# MainBoard.net
KiCad netlist of a schematic drawn in EAGLE
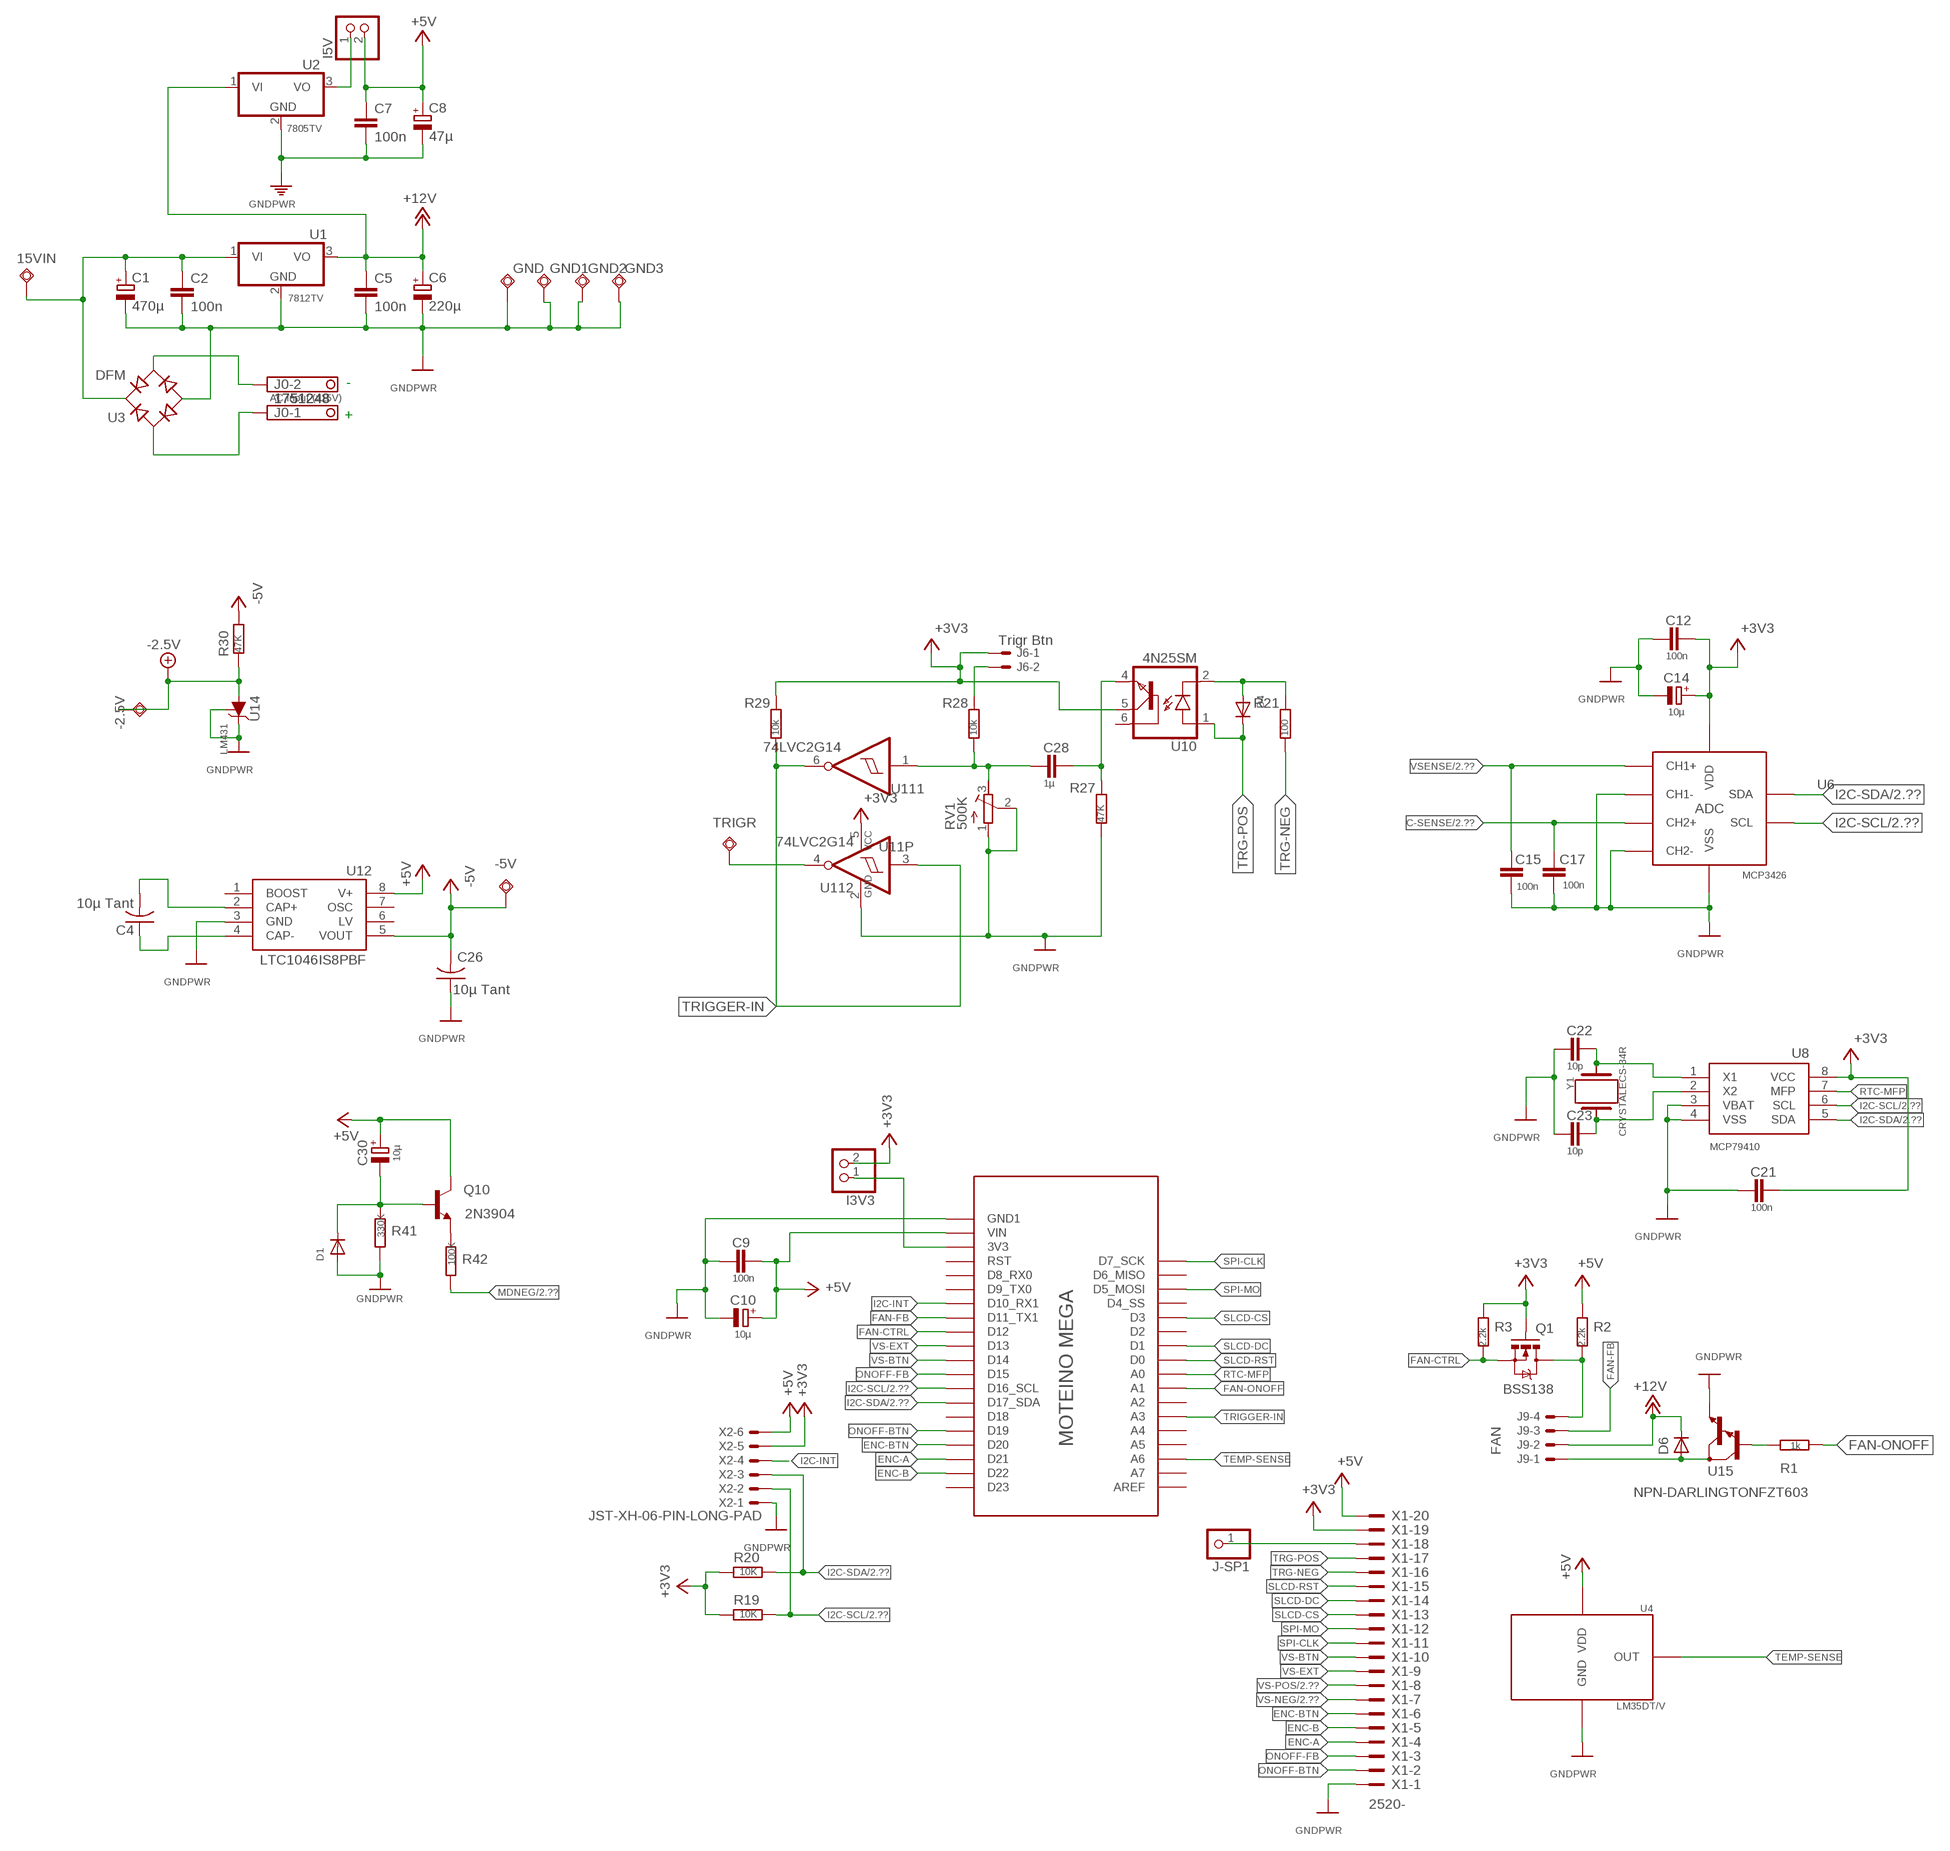
[diagram p0: schematic, sheet 1]
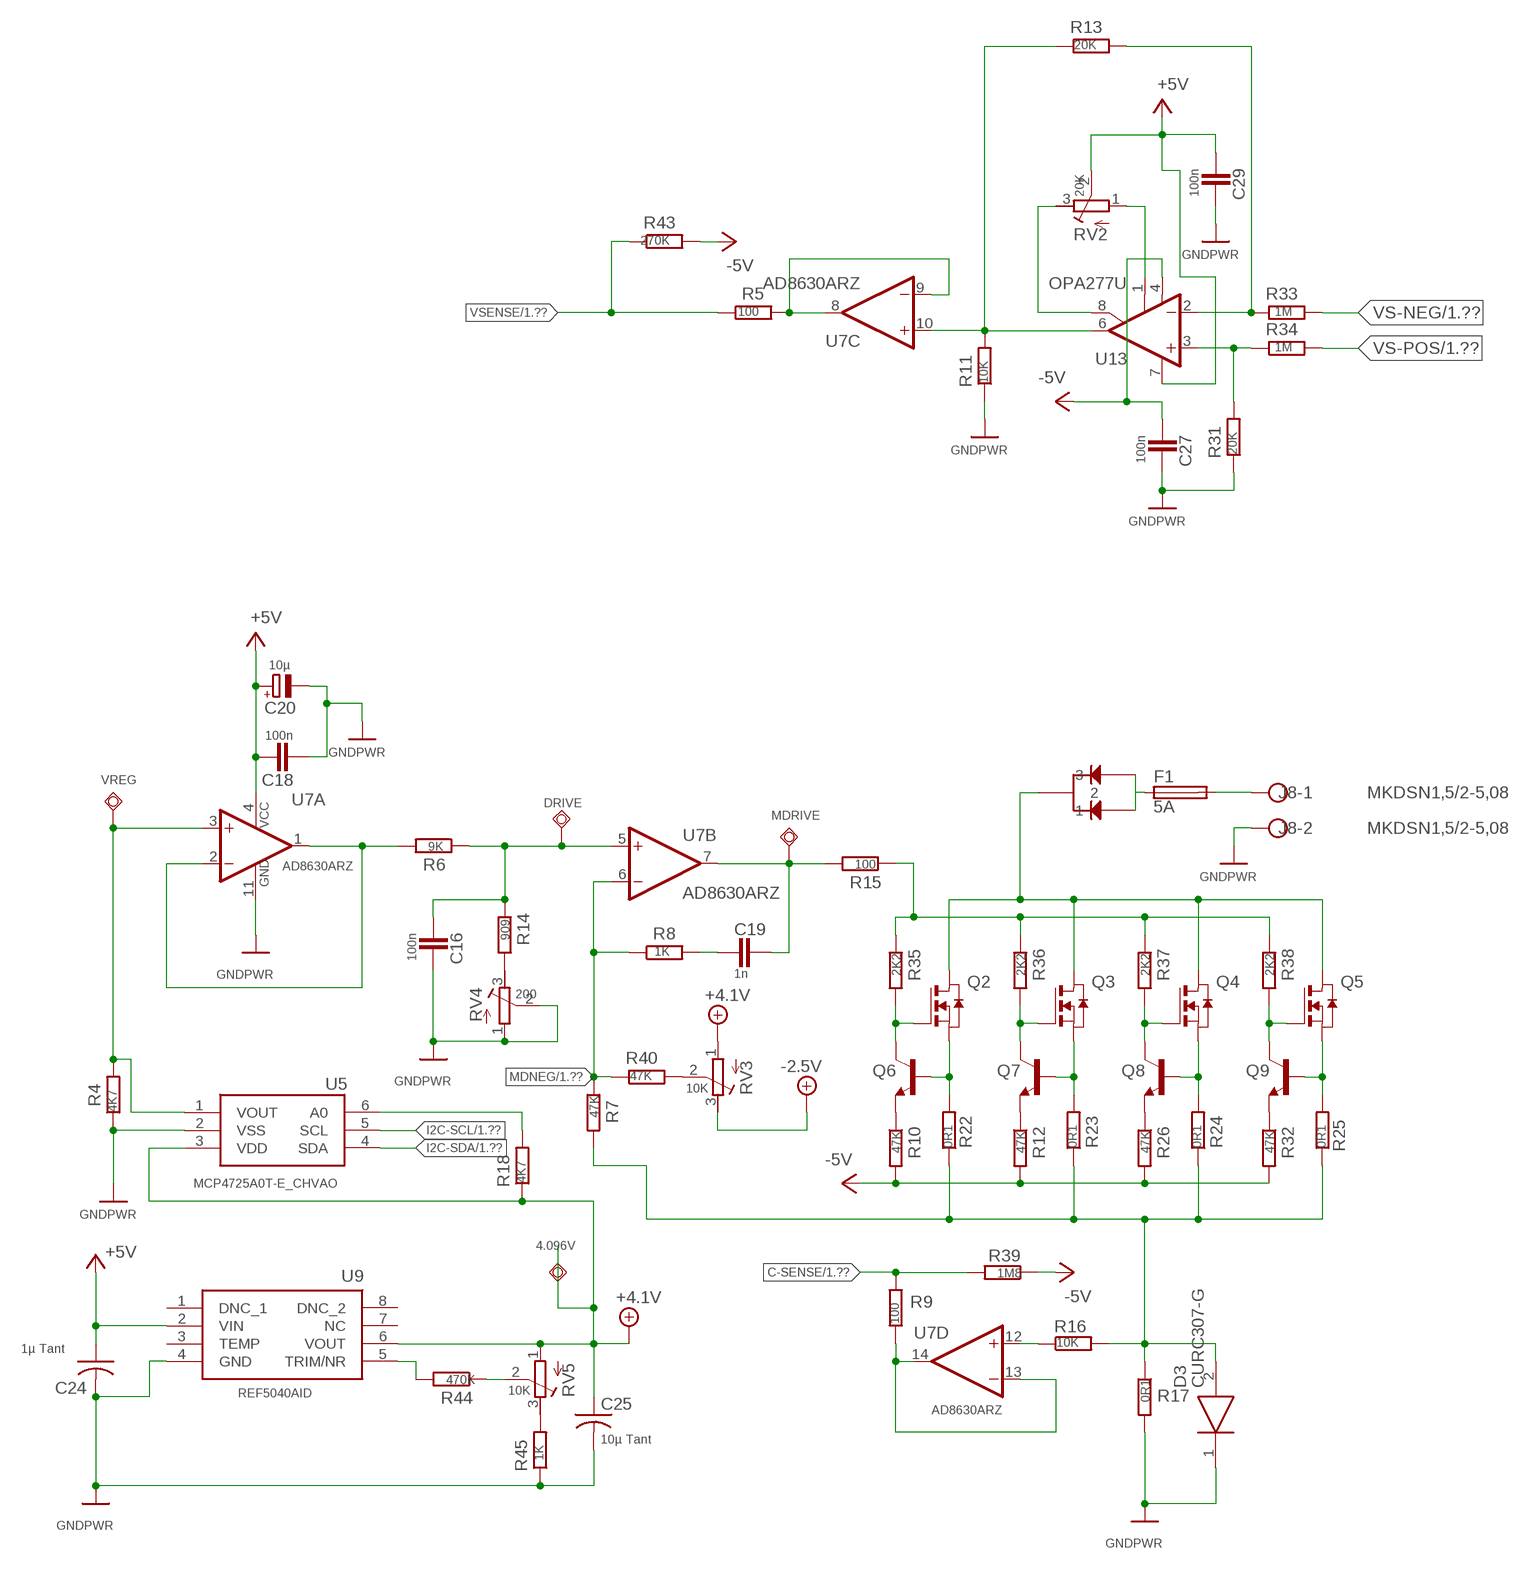
[diagram p1: schematic, sheet 2]

(export (version "E")
  (design (tool "Eeschema 10.0.6"))
  (components
    (comp (ref "4.096V")
      (value "TEST-POINT4952")
      (footprint "eagle-import:TP-KEYSTONE-4952")
      (libsource (lib "eagle-import") (part "TEST-POINT4952"))
    )
    (comp (ref "C16")
      (value "100n")
      (footprint "eagle-import:C0805K")
      (libsource (lib "eagle-import") (part "C-EUC0805K"))
    )
    (comp (ref "C18")
      (value "100n")
      (footprint "eagle-import:C0805K")
      (libsource (lib "eagle-import") (part "C-EUC0805K"))
    )
    (comp (ref "C19")
      (value "1n")
      (footprint "eagle-import:C0805K")
      (libsource (lib "eagle-import") (part "C-EUC0805K"))
    )
    (comp (ref "C20")
      (value "10µ")
      (footprint "eagle-import:E2-5")
      (libsource (lib "eagle-import") (part "CPOL-EUE2-5"))
    )
    (comp (ref "C24")
      (value "1µ Tant")
      (footprint "eagle-import:C1210")
      (libsource (lib "eagle-import") (part "C-USC1210"))
    )
    (comp (ref "C25")
      (value "10µ Tant")
      (footprint "eagle-import:C1210")
      (libsource (lib "eagle-import") (part "C-USC1210"))
    )
    (comp (ref "C27")
      (value "100n")
      (footprint "eagle-import:C0805K")
      (libsource (lib "eagle-import") (part "C-EUC0805K"))
    )
    (comp (ref "C29")
      (value "100n")
      (footprint "eagle-import:C0805K")
      (libsource (lib "eagle-import") (part "C-EUC0805K"))
    )
    (comp (ref "D3")
      (value "CURC307-G")
      (footprint "eagle-import:DIOM7959X262N")
      (fields (field (name "MOUSER_PART_NUMBER") "750-CURC307-G"))
      (libsource (lib "eagle-import") (part "CURC307-G"))
    )
    (comp (ref "D5")
      (value "MBR41H100CT/V")
      (footprint "eagle-import:TO220-VERT")
      (libsource (lib "eagle-import") (part "MBR41H100CT/V"))
    )
    (comp (ref "DRIVE")
      (value "TEST-POINT4952")
      (footprint "eagle-import:TP-KEYSTONE-4952")
      (libsource (lib "eagle-import") (part "TEST-POINT4952"))
    )
    (comp (ref "F1")
      (value "5A")
      (footprint "eagle-import:SHK20L")
      (libsource (lib "eagle-import") (part "SHK20L"))
    )
    (comp (ref "J8")
      (value "MKDSN1,5/2-5,08")
      (footprint "eagle-import:MKDSN1,5_2-5,08")
      (libsource (lib "eagle-import") (part "MKDSN1,5/2-5,08"))
    )
    (comp (ref "MDRIVE")
      (value "TEST-POINT4952")
      (footprint "eagle-import:TP-KEYSTONE-4952")
      (libsource (lib "eagle-import") (part "TEST-POINT4952"))
    )
    (comp (ref "Q2")
      (value "SUP70040E/V")
      (footprint "eagle-import:TO220-VERT")
      (libsource (lib "eagle-import") (part "SUP70040E/V"))
    )
    (comp (ref "Q3")
      (value "SUP70040E/V")
      (footprint "eagle-import:TO220-VERT")
      (libsource (lib "eagle-import") (part "SUP70040E/V"))
    )
    (comp (ref "Q4")
      (value "SUP70040E/V")
      (footprint "eagle-import:TO220-VERT")
      (libsource (lib "eagle-import") (part "SUP70040E/V"))
    )
    (comp (ref "Q5")
      (value "SUP70040E/V")
      (footprint "eagle-import:TO220-VERT")
      (libsource (lib "eagle-import") (part "SUP70040E/V"))
    )
    (comp (ref "Q6")
      (value "MPS2222A-NPN-TO92-CBE")
      (footprint "eagle-import:TO92-CBE")
      (libsource (lib "eagle-import") (part "-NPN-TO92-CBEMPS2222A"))
    )
    (comp (ref "Q7")
      (value "MPS2222A-NPN-TO92-CBE")
      (footprint "eagle-import:TO92-CBE")
      (libsource (lib "eagle-import") (part "-NPN-TO92-CBEMPS2222A"))
    )
    (comp (ref "Q8")
      (value "MPS2222A-NPN-TO92-CBE")
      (footprint "eagle-import:TO92-CBE")
      (libsource (lib "eagle-import") (part "-NPN-TO92-CBEMPS2222A"))
    )
    (comp (ref "Q9")
      (value "MPS2222A-NPN-TO92-CBE")
      (footprint "eagle-import:TO92-CBE")
      (libsource (lib "eagle-import") (part "-NPN-TO92-CBEMPS2222A"))
    )
    (comp (ref "R4")
      (value "4K7")
      (footprint "eagle-import:R0805")
      (libsource (lib "eagle-import") (part "R-EU_R0805"))
    )
    (comp (ref "R5")
      (value "100")
      (footprint "eagle-import:R0805")
      (libsource (lib "eagle-import") (part "R-EU_R0805"))
    )
    (comp (ref "R6")
      (value "9K")
      (footprint "eagle-import:R0805")
      (libsource (lib "eagle-import") (part "R-EU_R0805"))
    )
    (comp (ref "R7")
      (value "47K")
      (footprint "eagle-import:R0805")
      (libsource (lib "eagle-import") (part "R-EU_R0805"))
    )
    (comp (ref "R8")
      (value "1K")
      (footprint "eagle-import:R0805")
      (libsource (lib "eagle-import") (part "R-EU_R0805"))
    )
    (comp (ref "R9")
      (value "100")
      (footprint "eagle-import:R0805")
      (libsource (lib "eagle-import") (part "R-EU_R0805"))
    )
    (comp (ref "R10")
      (value "47K")
      (footprint "eagle-import:R0805")
      (libsource (lib "eagle-import") (part "R-EU_R0805"))
    )
    (comp (ref "R11")
      (value "10K")
      (footprint "eagle-import:R0805")
      (libsource (lib "eagle-import") (part "R-EU_R0805"))
    )
    (comp (ref "R12")
      (value "47K")
      (footprint "eagle-import:R0805")
      (libsource (lib "eagle-import") (part "R-EU_R0805"))
    )
    (comp (ref "R13")
      (value "20K")
      (footprint "eagle-import:R1206")
      (libsource (lib "eagle-import") (part "R-EU_R1206"))
    )
    (comp (ref "R14")
      (value "909")
      (footprint "eagle-import:R1206")
      (libsource (lib "eagle-import") (part "R-EU_R1206"))
    )
    (comp (ref "R15")
      (value "100")
      (footprint "eagle-import:R0805")
      (libsource (lib "eagle-import") (part "R-EU_R0805"))
    )
    (comp (ref "R16")
      (value "10K")
      (footprint "eagle-import:R0805")
      (libsource (lib "eagle-import") (part "R-EU_R0805"))
    )
    (comp (ref "R17")
      (value "0R1")
      (footprint "eagle-import:TO220-DPAC")
      (libsource (lib "eagle-import") (part "PWR220T-35"))
    )
    (comp (ref "R18")
      (value "4K7")
      (footprint "eagle-import:R0805")
      (libsource (lib "eagle-import") (part "R-EU_R0805"))
    )
    (comp (ref "R22")
      (value "0R1")
      (footprint "eagle-import:0750V")
      (libsource (lib "eagle-import") (part "RESISTOR0750V"))
    )
    (comp (ref "R23")
      (value "0R1")
      (footprint "eagle-import:0750V")
      (libsource (lib "eagle-import") (part "RESISTOR0750V"))
    )
    (comp (ref "R24")
      (value "0R1")
      (footprint "eagle-import:0750V")
      (libsource (lib "eagle-import") (part "RESISTOR0750V"))
    )
    (comp (ref "R25")
      (value "0R1")
      (footprint "eagle-import:0750V")
      (libsource (lib "eagle-import") (part "RESISTOR0750V"))
    )
    (comp (ref "R26")
      (value "47K")
      (footprint "eagle-import:R0805")
      (libsource (lib "eagle-import") (part "R-EU_R0805"))
    )
    (comp (ref "R31")
      (value "20K")
      (footprint "eagle-import:R1206")
      (libsource (lib "eagle-import") (part "R-EU_R1206"))
    )
    (comp (ref "R32")
      (value "47K")
      (footprint "eagle-import:R0805")
      (libsource (lib "eagle-import") (part "R-EU_R0805"))
    )
    (comp (ref "R33")
      (value "1M")
      (footprint "eagle-import:R1206")
      (libsource (lib "eagle-import") (part "R-EU_R1206"))
    )
    (comp (ref "R34")
      (value "1M")
      (footprint "eagle-import:R1206")
      (libsource (lib "eagle-import") (part "R-EU_R1206"))
    )
    (comp (ref "R35")
      (value "2K2")
      (footprint "eagle-import:R0805")
      (libsource (lib "eagle-import") (part "R-EU_R0805"))
    )
    (comp (ref "R36")
      (value "2K2")
      (footprint "eagle-import:R0805")
      (libsource (lib "eagle-import") (part "R-EU_R0805"))
    )
    (comp (ref "R37")
      (value "2K2")
      (footprint "eagle-import:R0805")
      (libsource (lib "eagle-import") (part "R-EU_R0805"))
    )
    (comp (ref "R38")
      (value "2K2")
      (footprint "eagle-import:R0805")
      (libsource (lib "eagle-import") (part "R-EU_R0805"))
    )
    (comp (ref "R39")
      (value "1M8")
      (footprint "eagle-import:R0805")
      (libsource (lib "eagle-import") (part "R-EU_R0805"))
    )
    (comp (ref "R40")
      (value "47K")
      (footprint "eagle-import:R1206")
      (libsource (lib "eagle-import") (part "R-EU_R1206"))
    )
    (comp (ref "R43")
      (value "270K")
      (footprint "eagle-import:R0805")
      (libsource (lib "eagle-import") (part "R-EU_R0805"))
    )
    (comp (ref "R44")
      (value "470K")
      (footprint "eagle-import:R0805")
      (libsource (lib "eagle-import") (part "R-EU_R0805"))
    )
    (comp (ref "R45")
      (value "1K")
      (footprint "eagle-import:R0805")
      (libsource (lib "eagle-import") (part "R-EU_R0805"))
    )
    (comp (ref "RV2")
      (value "20K")
      (footprint "eagle-import:RTRIM3296W")
      (libsource (lib "eagle-import") (part "R-TRIMM3296W"))
    )
    (comp (ref "RV3")
      (value "10K")
      (footprint "eagle-import:RTRIM3296W")
      (libsource (lib "eagle-import") (part "R-TRIMM3296W"))
    )
    (comp (ref "RV4")
      (value "200")
      (footprint "eagle-import:RTRIM3296W")
      (libsource (lib "eagle-import") (part "R-TRIMM3296W"))
    )
    (comp (ref "RV5")
      (value "10K")
      (footprint "eagle-import:RTRIM3296W")
      (libsource (lib "eagle-import") (part "R-TRIMM3296W"))
    )
    (comp (ref "U5")
      (value "MCP4725A0T-E_CHVAO")
      (footprint "eagle-import:SOT95P270X145-6N")
      (fields
        (field (name "MANUFACTURER_PART_NUMBER") "MCP4725A0T-E/CHVAO")
        (field (name "MOUSER_PART_NUMBER") "579-MCP4725A0TECHVAO")
      )
      (libsource (lib "eagle-import") (part "MCP4725A0T-E_CHVAO"))
    )
    (comp (ref "U7")
      (value "AD8630ARZ")
      (footprint "eagle-import:SO14")
      (libsource (lib "eagle-import") (part "AD8630ARZ"))
    )
    (comp (ref "U9")
      (value "REF5040AID")
      (footprint "eagle-import:SOIC127P600X175-8N")
      (fields (field (name "MOUSER_PART_NUMBER") "595-REF5040AID") (field (name "RS_PART_NUMBER") "0404326P"))
      (libsource (lib "eagle-import") (part "REF5040AID"))
    )
    (comp (ref "U13")
      (value "OPA277U")
      (footprint "eagle-import:SO08")
      (libsource (lib "eagle-import") (part "OPA277U"))
    )
    (comp (ref "VREG")
      (value "TEST-POINT4952")
      (footprint "eagle-import:TP-KEYSTONE-4952")
      (libsource (lib "eagle-import") (part "TEST-POINT4952"))
    )
    (comp (ref "-2.5V")
      (value "TEST-POINT4952")
      (footprint "eagle-import:TP-KEYSTONE-4952")
      (libsource (lib "eagle-import") (part "TEST-POINT4952"))
    )
    (comp (ref "-5V")
      (value "TEST-POINT4952")
      (footprint "eagle-import:TP-KEYSTONE-4952")
      (libsource (lib "eagle-import") (part "TEST-POINT4952"))
    )
    (comp (ref "15VIN")
      (value "TEST-POINT4952")
      (footprint "eagle-import:TP-KEYSTONE-4952")
      (libsource (lib "eagle-import") (part "TEST-POINT4952"))
    )
    (comp (ref "C1")
      (value "470µ")
      (footprint "eagle-import:E5-10,5")
      (libsource (lib "eagle-import") (part "CPOL-EUE5-10.5"))
    )
    (comp (ref "C2")
      (value "100n")
      (footprint "eagle-import:C0805K")
      (libsource (lib "eagle-import") (part "C-EUC0805K"))
    )
    (comp (ref "C4")
      (value "10µ Tant")
      (footprint "eagle-import:C1210")
      (libsource (lib "eagle-import") (part "C-USC1210"))
    )
    (comp (ref "C5")
      (value "100n")
      (footprint "eagle-import:C0805K")
      (libsource (lib "eagle-import") (part "C-EUC0805K"))
    )
    (comp (ref "C6")
      (value "220µ")
      (footprint "eagle-import:E5-10,5")
      (libsource (lib "eagle-import") (part "CPOL-EUE5-10.5"))
    )
    (comp (ref "C7")
      (value "100n")
      (footprint "eagle-import:C0805K")
      (libsource (lib "eagle-import") (part "C-EUC0805K"))
    )
    (comp (ref "C8")
      (value "47µ")
      (footprint "eagle-import:E5-5")
      (libsource (lib "eagle-import") (part "CPOL-EUE5-5"))
    )
    (comp (ref "C9")
      (value "100n")
      (footprint "eagle-import:C0805K")
      (libsource (lib "eagle-import") (part "C-EUC0805K"))
    )
    (comp (ref "C10")
      (value "10µ")
      (footprint "eagle-import:E2-5")
      (libsource (lib "eagle-import") (part "CPOL-EUE2-5"))
    )
    (comp (ref "C12")
      (value "100n")
      (footprint "eagle-import:C0805K")
      (libsource (lib "eagle-import") (part "C-EUC0805K"))
    )
    (comp (ref "C14")
      (value "10µ")
      (footprint "eagle-import:E2-5")
      (libsource (lib "eagle-import") (part "CPOL-EUE2-5"))
    )
    (comp (ref "C15")
      (value "100n")
      (footprint "eagle-import:C0805K")
      (libsource (lib "eagle-import") (part "C-EUC0805K"))
    )
    (comp (ref "C17")
      (value "100n")
      (footprint "eagle-import:C0805K")
      (libsource (lib "eagle-import") (part "C-EUC0805K"))
    )
    (comp (ref "C21")
      (value "100n")
      (footprint "eagle-import:C0805K")
      (libsource (lib "eagle-import") (part "C-EUC0805K"))
    )
    (comp (ref "C22")
      (value "10p")
      (footprint "eagle-import:C0805K")
      (libsource (lib "eagle-import") (part "C-EUC0805K"))
    )
    (comp (ref "C23")
      (value "10p")
      (footprint "eagle-import:C0805K")
      (libsource (lib "eagle-import") (part "C-EUC0805K"))
    )
    (comp (ref "C26")
      (value "10µ Tant")
      (footprint "eagle-import:C1210")
      (libsource (lib "eagle-import") (part "C-USC1210"))
    )
    (comp (ref "C28")
      (value "1µ")
      (footprint "eagle-import:C0805K")
      (libsource (lib "eagle-import") (part "C-EUC0805K"))
    )
    (comp (ref "C30")
      (value "10µ")
      (footprint "eagle-import:E2-5")
      (libsource (lib "eagle-import") (part "CPOL-EUE2-5"))
    )
    (comp (ref "D1")
      (value "DIODESOD-323F")
      (footprint "eagle-import:SOD-323F")
      (libsource (lib "eagle-import") (part "DIODESOD-323F"))
    )
    (comp (ref "D4")
      (value "DIODESOD-323F")
      (footprint "eagle-import:SOD-323F")
      (libsource (lib "eagle-import") (part "DIODESOD-323F"))
    )
    (comp (ref "D6")
      (value "DIODE_SOD-123FL")
      (footprint "eagle-import:SOD-123FL")
      (libsource (lib "eagle-import") (part "DIODE_SOD-123FL"))
    )
    (comp (ref "GND")
      (value "TEST-POINT4952")
      (footprint "eagle-import:TP-KEYSTONE-4952")
      (libsource (lib "eagle-import") (part "TEST-POINT4952"))
    )
    (comp (ref "GND1")
      (value "TEST-POINT4952")
      (footprint "eagle-import:TP-KEYSTONE-4952")
      (libsource (lib "eagle-import") (part "TEST-POINT4952"))
    )
    (comp (ref "GND2")
      (value "TEST-POINT4952")
      (footprint "eagle-import:TP-KEYSTONE-4952")
      (libsource (lib "eagle-import") (part "TEST-POINT4952"))
    )
    (comp (ref "GND3")
      (value "TEST-POINT4952")
      (footprint "eagle-import:TP-KEYSTONE-4952")
      (libsource (lib "eagle-import") (part "TEST-POINT4952"))
    )
    (comp (ref "I3V3")
      (value "PINHD-1X2")
      (footprint "eagle-import:1X02")
      (libsource (lib "eagle-import") (part "PINHD-1X2"))
    )
    (comp (ref "I5V")
      (value "PINHD-1X2")
      (footprint "eagle-import:1X02")
      (libsource (lib "eagle-import") (part "PINHD-1X2"))
    )
    (comp (ref "J-SP1")
      (value "PINHD-1X1")
      (footprint "eagle-import:1X01")
      (libsource (lib "eagle-import") (part "PINHD-1X1"))
    )
    (comp (ref "J0")
      (value "1751248")
      (footprint "eagle-import:1751248")
      (libsource (lib "eagle-import") (part "1751248"))
    )
    (comp (ref "J6")
      (value "Trigr Btn")
      (footprint "eagle-import:JST-XH-02-PACKAGE-ROUND-PAD")
      (libsource (lib "eagle-import") (part "JST-XH-02-PIN-ROUND-PAD"))
    )
    (comp (ref "J9")
      (value "FAN")
      (footprint "eagle-import:JST-XH-04-PACKAGE-ROUND-PAD")
      (libsource (lib "eagle-import") (part "JST-XH-04-PIN-ROUND-PAD"))
    )
    (comp (ref "Q1")
      (value "BSS138")
      (footprint "eagle-import:SOT23")
      (libsource (lib "eagle-import") (part "MOSFET-NCHANNELBSS138"))
    )
    (comp (ref "Q10")
      (value "2N3904")
      (footprint "eagle-import:TO92")
      (libsource (lib "eagle-import") (part "2N3904"))
    )
    (comp (ref "R1")
      (value "1k")
      (footprint "eagle-import:R0805")
      (libsource (lib "eagle-import") (part "R-EU_R0805"))
    )
    (comp (ref "R2")
      (value "2.2k")
      (footprint "eagle-import:R0805")
      (libsource (lib "eagle-import") (part "R-EU_R0805"))
    )
    (comp (ref "R3")
      (value "2.2k")
      (footprint "eagle-import:R0805")
      (libsource (lib "eagle-import") (part "R-EU_R0805"))
    )
    (comp (ref "R19")
      (value "10K")
      (footprint "eagle-import:R0805")
      (libsource (lib "eagle-import") (part "R-EU_R0805"))
    )
    (comp (ref "R20")
      (value "10K")
      (footprint "eagle-import:R0805")
      (libsource (lib "eagle-import") (part "R-EU_R0805"))
    )
    (comp (ref "R21")
      (value "100")
      (footprint "eagle-import:R0805")
      (libsource (lib "eagle-import") (part "R-EU_R0805"))
    )
    (comp (ref "R27")
      (value "47K")
      (footprint "eagle-import:R0805")
      (libsource (lib "eagle-import") (part "R-EU_R0805"))
    )
    (comp (ref "R28")
      (value "10k")
      (footprint "eagle-import:R0805")
      (libsource (lib "eagle-import") (part "R-EU_R0805"))
    )
    (comp (ref "R29")
      (value "10k")
      (footprint "eagle-import:R0805")
      (libsource (lib "eagle-import") (part "R-EU_R0805"))
    )
    (comp (ref "R30")
      (value "47K")
      (footprint "eagle-import:R0805")
      (libsource (lib "eagle-import") (part "R-EU_R0805"))
    )
    (comp (ref "R41")
      (value "330K")
      (footprint "eagle-import:R0805")
      (libsource (lib "eagle-import") (part "R-EU_R0805"))
    )
    (comp (ref "R42")
      (value "100K")
      (footprint "eagle-import:R0805")
      (libsource (lib "eagle-import") (part "R-EU_R0805"))
    )
    (comp (ref "RV1")
      (value "500K")
      (footprint "eagle-import:RTRIM3296W")
      (libsource (lib "eagle-import") (part "R-TRIMM3296W"))
    )
    (comp (ref "TRIGR")
      (value "TEST-POINT4952")
      (footprint "eagle-import:TP-KEYSTONE-4952")
      (libsource (lib "eagle-import") (part "TEST-POINT4952"))
    )
    (comp (ref "U$1")
      (value "MOTEINO_MEGA_SIMPLE")
      (footprint "eagle-import:MOTEINO_MEGA_SIMPLE")
      (libsource (lib "eagle-import") (part "MOTEINO_MEGA_SIMPLE"))
    )
    (comp (ref "U1")
      (value "7812TV")
      (footprint "eagle-import:TO220V")
      (libsource (lib "eagle-import") (part "78TV12"))
    )
    (comp (ref "U2")
      (value "7805TV")
      (footprint "eagle-import:TO220V")
      (libsource (lib "eagle-import") (part "78TV05"))
    )
    (comp (ref "U3")
      (value "DFM")
      (footprint "eagle-import:DFM")
      (libsource (lib "eagle-import") (part "DFM"))
    )
    (comp (ref "U4")
      (value "LM35DT/V")
      (footprint "eagle-import:TO220V")
      (libsource (lib "eagle-import") (part "LM35DT/V"))
    )
    (comp (ref "U6")
      (value "MCP3426")
      (footprint "eagle-import:SO8")
      (libsource (lib "eagle-import") (part "MCP3426"))
    )
    (comp (ref "U8")
      (value "MCP79410")
      (footprint "eagle-import:SOIC127P600X175-8N")
      (fields
        (field (name "MANUFACTURER_PART_NUMBER") "MCP79410-I/SN")
        (field (name "MOUSER_PART_NUMBER") "579-MCP79410-I/SN")
        (field (name "RS_PART_NUMBER") "7263949P")
      )
      (libsource (lib "eagle-import") (part "MCP79410-I_SN"))
    )
    (comp (ref "U10")
      (value "4N25SM")
      (footprint "eagle-import:DIL6-SMD")
      (fields (field (name "MF") "FAIRCHILD SEMICONDUCTOR"))
      (libsource (lib "eagle-import") (part "4N?MS25"))
    )
    (comp (ref "U11")
      (value "74LVC2G14")
      (footprint "eagle-import:SOT23-6")
      (libsource (lib "eagle-import") (part "74LVC2G14"))
    )
    (comp (ref "U12")
      (value "LTC1046IS8PBF")
      (footprint "eagle-import:SOIC127P599X175-8N")
      (libsource (lib "eagle-import") (part "LTC1046IS8PBF"))
    )
    (comp (ref "U14")
      (value "LM431")
      (footprint "eagle-import:SOT23")
      (libsource (lib "eagle-import") (part "LM431"))
    )
    (comp (ref "U15")
      (value "NPN-DARLINGTONFZT603")
      (footprint "eagle-import:SOT223")
      (libsource (lib "eagle-import") (part "NPN-DARLINGTONFZT603"))
    )
    (comp (ref "X1")
      (value "2520-")
      (footprint "eagle-import:PAK100_2500-20")
      (libsource (lib "eagle-import") (part "2520-"))
    )
    (comp (ref "X2")
      (value "JST-XH-06-PIN-LONG-PAD")
      (footprint "eagle-import:JST-XH-06-PACKAGE-LONG-PAD")
      (libsource (lib "eagle-import") (part "JST-XH-06-PIN-LONG-PAD"))
    )
    (comp (ref "Y1")
      (value "CRYSTALECS-34R")
      (footprint "eagle-import:ECS32712534RRTR")
      (libsource (lib "eagle-import") (part "CRYSTALECS-34R"))
    )
  )
  (nets
    (net (code "1") (name "+3V3") (class "Default")
      (node (ref "C12") (pin "1") (pinfunction "1_1") (pintype "passive"))
      (node (ref "C14") (pin "+") (pinfunction "+_+") (pintype "passive"))
      (node (ref "C21") (pin "1") (pinfunction "1_1") (pintype "passive"))
      (node (ref "I3V3") (pin "2") (pinfunction "2_2") (pintype "passive"))
      (node (ref "J6") (pin "1") (pinfunction "S_1") (pintype "passive"))
      (node (ref "Q1") (pin "1") (pinfunction "G_1") (pintype "passive"))
      (node (ref "R19") (pin "2") (pinfunction "2_2") (pintype "passive"))
      (node (ref "R20") (pin "2") (pinfunction "2_2") (pintype "passive"))
      (node (ref "R29") (pin "2") (pinfunction "2_2") (pintype "passive"))
      (node (ref "R3") (pin "2") (pinfunction "2_2") (pintype "passive"))
      (node (ref "U10") (pin "5") (pinfunction "COL_5") (pintype "passive"))
      (node (ref "U11") (pin "5") (pinfunction "VCC_5") (pintype "power_in"))
      (node (ref "U6") (pin "3") (pinfunction "VDD_3") (pintype "bidirectional"))
      (node (ref "U8") (pin "8") (pinfunction "VCC_8") (pintype "power_in"))
      (node (ref "X1") (pin "19") (pinfunction "KL_19") (pintype "passive"))
      (node (ref "X2") (pin "5") (pinfunction "S_5") (pintype "passive"))
    )
    (net (code "2") (name "+4.1V") (class "Default")
      (node (ref "4.096V") (pin "P$1") (pinfunction "TP_P$1") (pintype "bidirectional"))
      (node (ref "C25") (pin "1") (pinfunction "1_1") (pintype "passive"))
      (node (ref "R18") (pin "1") (pinfunction "1_1") (pintype "passive"))
      (node (ref "RV3") (pin "1") (pinfunction "A_1") (pintype "passive"))
      (node (ref "RV5") (pin "1") (pinfunction "A_1") (pintype "passive"))
      (node (ref "U5") (pin "3") (pinfunction "VDD_3") (pintype "bidirectional"))
      (node (ref "U9") (pin "6") (pinfunction "VOUT_6") (pintype "bidirectional"))
    )
    (net (code "3") (name "+5V") (class "Default")
      (node (ref "C10") (pin "+") (pinfunction "+_+") (pintype "passive"))
      (node (ref "C18") (pin "1") (pinfunction "1_1") (pintype "passive"))
      (node (ref "C20") (pin "+") (pinfunction "+_+") (pintype "passive"))
      (node (ref "C24") (pin "1") (pinfunction "1_1") (pintype "passive"))
      (node (ref "C29") (pin "2") (pinfunction "2_2") (pintype "passive"))
      (node (ref "C30") (pin "+") (pinfunction "+_+") (pintype "passive"))
      (node (ref "C7") (pin "1") (pinfunction "1_1") (pintype "passive"))
      (node (ref "C8") (pin "+") (pinfunction "+_+") (pintype "passive"))
      (node (ref "C9") (pin "1") (pinfunction "1_1") (pintype "passive"))
      (node (ref "I5V") (pin "2") (pinfunction "2_2") (pintype "passive"))
      (node (ref "Q10") (pin "1") (pinfunction "C_1") (pintype "passive"))
      (node (ref "R2") (pin "2") (pinfunction "2_2") (pintype "passive"))
      (node (ref "RV2") (pin "2") (pinfunction "S_2") (pintype "passive"))
      (node (ref "U$1") (pin "VIN") (pinfunction "VIN_VIN") (pintype "bidirectional"))
      (node (ref "U$1") (pin "VIN_2") (pinfunction "VIN_VIN_2") (pintype "bidirectional"))
      (node (ref "U12") (pin "8") (pinfunction "V+_8") (pintype "bidirectional"))
      (node (ref "U13") (pin "7") (pinfunction "V+_7") (pintype "power_in"))
      (node (ref "U4") (pin "1") (pinfunction "VDD_1") (pintype "power_in"))
      (node (ref "U7") (pin "4") (pinfunction "VCC_4") (pintype "power_in"))
      (node (ref "U9") (pin "2") (pinfunction "VIN_2") (pintype "bidirectional"))
      (node (ref "X1") (pin "20") (pinfunction "KL_20") (pintype "passive"))
      (node (ref "X2") (pin "6") (pinfunction "S_6") (pintype "passive"))
    )
    (net (code "4") (name "+12V") (class "Default")
      (node (ref "C5") (pin "1") (pinfunction "1_1") (pintype "passive"))
      (node (ref "C6") (pin "+") (pinfunction "+_+") (pintype "passive"))
      (node (ref "D6") (pin "C") (pinfunction "C_C") (pintype "passive"))
      (node (ref "J9") (pin "2") (pinfunction "S_2") (pintype "passive"))
      (node (ref "U1") (pin "3") (pinfunction "VO_3") (pintype "passive"))
      (node (ref "U2") (pin "1") (pinfunction "VI_1") (pintype "input"))
    )
    (net (code "5") (name "-2.5V") (class "Default")
      (node (ref "-2.5V") (pin "P$1") (pinfunction "TP_P$1") (pintype "bidirectional"))
      (node (ref "R30") (pin "1") (pinfunction "1_1") (pintype "passive"))
      (node (ref "RV3") (pin "3") (pinfunction "E_3") (pintype "passive"))
      (node (ref "U14") (pin "3") (pinfunction "A_3") (pintype "passive"))
    )
    (net (code "6") (name "-5V") (class "Default")
      (node (ref "-5V") (pin "P$1") (pinfunction "TP_P$1") (pintype "bidirectional"))
      (node (ref "C26") (pin "2") (pinfunction "2_2") (pintype "passive"))
      (node (ref "C27") (pin "2") (pinfunction "2_2") (pintype "passive"))
      (node (ref "R10") (pin "2") (pinfunction "2_2") (pintype "passive"))
      (node (ref "R12") (pin "2") (pinfunction "2_2") (pintype "passive"))
      (node (ref "R26") (pin "2") (pinfunction "2_2") (pintype "passive"))
      (node (ref "R30") (pin "2") (pinfunction "2_2") (pintype "passive"))
      (node (ref "R32") (pin "2") (pinfunction "2_2") (pintype "passive"))
      (node (ref "R39") (pin "1") (pinfunction "1_1") (pintype "passive"))
      (node (ref "R43") (pin "2") (pinfunction "2_2") (pintype "passive"))
      (node (ref "U12") (pin "5") (pinfunction "VOUT_5") (pintype "bidirectional"))
      (node (ref "U13") (pin "4") (pinfunction "V-_4") (pintype "power_in"))
    )
    (net (code "7") (name "C-SENSE") (class "Default")
      (node (ref "C17") (pin "2") (pinfunction "2_2") (pintype "passive"))
      (node (ref "R39") (pin "2") (pinfunction "2_2") (pintype "passive"))
      (node (ref "R9") (pin "2") (pinfunction "2_2") (pintype "passive"))
      (node (ref "U6") (pin "7") (pinfunction "CH2+_7") (pintype "bidirectional"))
    )
    (net (code "8") (name "ENC-A") (class "Default")
      (node (ref "U$1") (pin "D21") (pinfunction "D21_D21") (pintype "bidirectional"))
      (node (ref "X1") (pin "4") (pinfunction "KL_4") (pintype "passive"))
    )
    (net (code "9") (name "ENC-B") (class "Default")
      (node (ref "U$1") (pin "D22") (pinfunction "D22_D22") (pintype "bidirectional"))
      (node (ref "X1") (pin "5") (pinfunction "KL_5") (pintype "passive"))
    )
    (net (code "10") (name "ENC-BTN") (class "Default")
      (node (ref "U$1") (pin "D20") (pinfunction "D20_D20") (pintype "bidirectional"))
      (node (ref "X1") (pin "6") (pinfunction "KL_6") (pintype "passive"))
    )
    (net (code "11") (name "FAN-CTRL") (class "Default")
      (node (ref "Q1") (pin "2") (pinfunction "S_2") (pintype "passive"))
      (node (ref "R3") (pin "1") (pinfunction "1_1") (pintype "passive"))
      (node (ref "U$1") (pin "D12") (pinfunction "D12_D12") (pintype "bidirectional"))
    )
    (net (code "12") (name "FAN-FB") (class "Default")
      (node (ref "J9") (pin "3") (pinfunction "S_3") (pintype "passive"))
      (node (ref "U$1") (pin "D11") (pinfunction "D11_TX1_D11") (pintype "bidirectional"))
    )
    (net (code "13") (name "FAN-ONOFF") (class "Default")
      (node (ref "R1") (pin "1") (pinfunction "1_1") (pintype "passive"))
      (node (ref "U$1") (pin "A1") (pinfunction "A1_A1") (pintype "bidirectional"))
    )
    (net (code "14") (name "GND") (class "Default")
      (node (ref "C1") (pin "-") (pinfunction "-_-") (pintype "passive"))
      (node (ref "C10") (pin "-") (pinfunction "-_-") (pintype "passive"))
      (node (ref "C12") (pin "2") (pinfunction "2_2") (pintype "passive"))
      (node (ref "C14") (pin "-") (pinfunction "-_-") (pintype "passive"))
      (node (ref "C15") (pin "2") (pinfunction "2_2") (pintype "passive"))
      (node (ref "C16") (pin "1") (pinfunction "1_1") (pintype "passive"))
      (node (ref "C17") (pin "1") (pinfunction "1_1") (pintype "passive"))
      (node (ref "C18") (pin "2") (pinfunction "2_2") (pintype "passive"))
      (node (ref "C2") (pin "2") (pinfunction "2_2") (pintype "passive"))
      (node (ref "C20") (pin "-") (pinfunction "-_-") (pintype "passive"))
      (node (ref "C21") (pin "2") (pinfunction "2_2") (pintype "passive"))
      (node (ref "C22") (pin "2") (pinfunction "2_2") (pintype "passive"))
      (node (ref "C23") (pin "2") (pinfunction "2_2") (pintype "passive"))
      (node (ref "C24") (pin "2") (pinfunction "2_2") (pintype "passive"))
      (node (ref "C25") (pin "2") (pinfunction "2_2") (pintype "passive"))
      (node (ref "C26") (pin "1") (pinfunction "1_1") (pintype "passive"))
      (node (ref "C27") (pin "1") (pinfunction "1_1") (pintype "passive"))
      (node (ref "C29") (pin "1") (pinfunction "1_1") (pintype "passive"))
      (node (ref "C5") (pin "2") (pinfunction "2_2") (pintype "passive"))
      (node (ref "C6") (pin "-") (pinfunction "-_-") (pintype "passive"))
      (node (ref "C7") (pin "2") (pinfunction "2_2") (pintype "passive"))
      (node (ref "C8") (pin "-") (pinfunction "-_-") (pintype "passive"))
      (node (ref "C9") (pin "2") (pinfunction "2_2") (pintype "passive"))
      (node (ref "D1") (pin "A") (pinfunction "A_A") (pintype "passive"))
      (node (ref "D3") (pin "1") (pinfunction "K_1") (pintype "bidirectional"))
      (node (ref "GND") (pin "P$1") (pinfunction "TP_P$1") (pintype "bidirectional"))
      (node (ref "GND1") (pin "P$1") (pinfunction "TP_P$1") (pintype "bidirectional"))
      (node (ref "GND2") (pin "P$1") (pinfunction "TP_P$1") (pintype "bidirectional"))
      (node (ref "GND3") (pin "P$1") (pinfunction "TP_P$1") (pintype "bidirectional"))
      (node (ref "J8") (pin "2") (pinfunction "KL_2") (pintype "passive"))
      (node (ref "R11") (pin "1") (pinfunction "1_1") (pintype "passive"))
      (node (ref "R17") (pin "2") (pinfunction "2_2") (pintype "passive"))
      (node (ref "R27") (pin "1") (pinfunction "1_1") (pintype "passive"))
      (node (ref "R31") (pin "1") (pinfunction "1_1") (pintype "passive"))
      (node (ref "R4") (pin "1") (pinfunction "1_1") (pintype "passive"))
      (node (ref "R41") (pin "2") (pinfunction "2_2") (pintype "passive"))
      (node (ref "R45") (pin "1") (pinfunction "1_1") (pintype "passive"))
      (node (ref "RV1") (pin "1") (pinfunction "A_1") (pintype "passive"))
      (node (ref "RV1") (pin "2") (pinfunction "S_2") (pintype "passive"))
      (node (ref "RV4") (pin "1") (pinfunction "A_1") (pintype "passive"))
      (node (ref "RV4") (pin "2") (pinfunction "S_2") (pintype "passive"))
      (node (ref "U$1") (pin "GND1") (pinfunction "GND1_GND1") (pintype "bidirectional"))
      (node (ref "U$1") (pin "GND_2") (pinfunction "GND1_GND_2") (pintype "bidirectional"))
      (node (ref "U1") (pin "2") (pinfunction "GND_2") (pintype "passive"))
      (node (ref "U11") (pin "2") (pinfunction "GND_2") (pintype "power_in"))
      (node (ref "U12") (pin "3") (pinfunction "GND_3") (pintype "bidirectional"))
      (node (ref "U14") (pin "1") (pinfunction "C_1") (pintype "passive"))
      (node (ref "U14") (pin "2") (pinfunction "ADJ_2") (pintype "bidirectional"))
      (node (ref "U15") (pin "3") (pinfunction "E_3") (pintype "passive"))
      (node (ref "U2") (pin "2") (pinfunction "GND_2") (pintype "passive"))
      (node (ref "U3") (pin "-") (pinfunction "-_-") (pintype "passive"))
      (node (ref "U4") (pin "2") (pinfunction "GND_2") (pintype "power_in"))
      (node (ref "U5") (pin "2") (pinfunction "VSS_2") (pintype "bidirectional"))
      (node (ref "U6") (pin "2") (pinfunction "CH1-_2") (pintype "bidirectional"))
      (node (ref "U6") (pin "6") (pinfunction "VSS_6") (pintype "bidirectional"))
      (node (ref "U6") (pin "8") (pinfunction "CH2-_8") (pintype "bidirectional"))
      (node (ref "U7") (pin "11") (pinfunction "GND_11") (pintype "power_in"))
      (node (ref "U8") (pin "3") (pinfunction "VBAT_3") (pintype "bidirectional"))
      (node (ref "U8") (pin "4") (pinfunction "VSS_4") (pintype "power_in"))
      (node (ref "U9") (pin "4") (pinfunction "GND_4") (pintype "bidirectional"))
      (node (ref "X1") (pin "1") (pinfunction "KL_1") (pintype "passive"))
      (node (ref "X2") (pin "1") (pinfunction "S_1") (pintype "passive"))
    )
    (net (code "15") (name "I2C-INT") (class "Default")
      (node (ref "U$1") (pin "D10") (pinfunction "D10_RX1_D10") (pintype "bidirectional"))
      (node (ref "X2") (pin "4") (pinfunction "S_4") (pintype "passive"))
    )
    (net (code "16") (name "I2C-SCL") (class "Default")
      (node (ref "R19") (pin "1") (pinfunction "1_1") (pintype "passive"))
      (node (ref "U$1") (pin "D16") (pinfunction "D16_SCL_D16") (pintype "bidirectional"))
      (node (ref "U5") (pin "5") (pinfunction "SCL_5") (pintype "bidirectional"))
      (node (ref "U6") (pin "5") (pinfunction "SCL_5") (pintype "bidirectional"))
      (node (ref "U8") (pin "6") (pinfunction "SCL_6") (pintype "bidirectional"))
      (node (ref "X2") (pin "2") (pinfunction "S_2") (pintype "passive"))
    )
    (net (code "17") (name "I2C-SDA") (class "Default")
      (node (ref "R20") (pin "1") (pinfunction "1_1") (pintype "passive"))
      (node (ref "U$1") (pin "D17") (pinfunction "D17_SDA_D17") (pintype "bidirectional"))
      (node (ref "U5") (pin "4") (pinfunction "SDA_4") (pintype "bidirectional"))
      (node (ref "U6") (pin "4") (pinfunction "SDA_4") (pintype "bidirectional"))
      (node (ref "U8") (pin "5") (pinfunction "SDA_5") (pintype "bidirectional"))
      (node (ref "X2") (pin "3") (pinfunction "S_3") (pintype "passive"))
    )
    (net (code "18") (name "MDNEG") (class "Default")
      (node (ref "R40") (pin "1") (pinfunction "1_1") (pintype "passive"))
      (node (ref "R42") (pin "2") (pinfunction "2_2") (pintype "passive"))
      (node (ref "R7") (pin "1") (pinfunction "1_1") (pintype "passive"))
      (node (ref "R8") (pin "1") (pinfunction "1_1") (pintype "passive"))
      (node (ref "U7") (pin "6") (pinfunction "-IN_6") (pintype "input"))
    )
    (net (code "19") (name "Net-(15VIN-TP)") (class "Default")
      (node (ref "15VIN") (pin "P$1") (pinfunction "TP_P$1") (pintype "bidirectional"))
      (node (ref "C1") (pin "+") (pinfunction "+_+") (pintype "passive"))
      (node (ref "C2") (pin "1") (pinfunction "1_1") (pintype "passive"))
      (node (ref "U1") (pin "1") (pinfunction "VI_1") (pintype "input"))
      (node (ref "U3") (pin "+") (pinfunction "+_+") (pintype "passive"))
    )
    (net (code "20") (name "Net-(C19-Pad2)") (class "Default")
      (node (ref "C19") (pin "2") (pinfunction "2_2") (pintype "passive"))
      (node (ref "R8") (pin "2") (pinfunction "2_2") (pintype "passive"))
    )
    (net (code "21") (name "Net-(D3-A)") (class "Default")
      (node (ref "D3") (pin "2") (pinfunction "A_2") (pintype "bidirectional"))
      (node (ref "R16") (pin "2") (pinfunction "2_2") (pintype "passive"))
      (node (ref "R17") (pin "1") (pinfunction "1_1") (pintype "passive"))
      (node (ref "R22") (pin "1") (pinfunction "1_1") (pintype "passive"))
      (node (ref "R23") (pin "1") (pinfunction "1_1") (pintype "passive"))
      (node (ref "R24") (pin "1") (pinfunction "1_1") (pintype "passive"))
      (node (ref "R25") (pin "1") (pinfunction "1_1") (pintype "passive"))
      (node (ref "R7") (pin "2") (pinfunction "2_2") (pintype "passive"))
    )
    (net (code "22") (name "Net-(D5-Pad1)") (class "Default")
      (node (ref "D5") (pin "1") (pinfunction "1_1") (pintype "bidirectional"))
      (node (ref "D5") (pin "3") (pinfunction "3_3") (pintype "bidirectional"))
      (node (ref "F1") (pin "1A") (pinfunction "1_1A") (pintype "passive"))
      (node (ref "F1") (pin "1B") (pinfunction "1_1B") (pintype "passive"))
    )
    (net (code "23") (name "Net-(DRIVE-TP)") (class "Default")
      (node (ref "C16") (pin "2") (pinfunction "2_2") (pintype "passive"))
      (node (ref "DRIVE") (pin "P$1") (pinfunction "TP_P$1") (pintype "bidirectional"))
      (node (ref "R14") (pin "1") (pinfunction "1_1") (pintype "passive"))
      (node (ref "R6") (pin "1") (pinfunction "1_1") (pintype "passive"))
      (node (ref "U7") (pin "5") (pinfunction "+IN_5") (pintype "input"))
    )
    (net (code "24") (name "Net-(I3V3-Pad1)") (class "Default")
      (node (ref "I3V3") (pin "1") (pinfunction "1_1") (pintype "passive"))
      (node (ref "U$1") (pin "3V3") (pinfunction "3V3_3V3") (pintype "bidirectional"))
      (node (ref "U$1") (pin "3V3_2") (pinfunction "3V3_3V3_2") (pintype "bidirectional"))
    )
    (net (code "25") (name "Net-(J0A-K)") (class "Default")
      (node (ref "J0") (pin "1") (pinfunction "K_1") (pintype "passive"))
      (node (ref "U3") (pin "A1") (pinfunction "AC1_A1") (pintype "passive"))
    )
    (net (code "26") (name "Net-(J0B-K)") (class "Default")
      (node (ref "J0") (pin "2") (pinfunction "K_2") (pintype "passive"))
      (node (ref "U3") (pin "A2") (pinfunction "AC2_A2") (pintype "passive"))
    )
    (net (code "27") (name "Net-(J6B-S)") (class "Default")
      (node (ref "J6") (pin "2") (pinfunction "S_2") (pintype "passive"))
      (node (ref "R28") (pin "2") (pinfunction "2_2") (pintype "passive"))
    )
    (net (code "28") (name "Net-(J8A-KL)") (class "Default")
      (node (ref "F1") (pin "2A") (pinfunction "2_2A") (pintype "passive"))
      (node (ref "F1") (pin "2B") (pinfunction "2_2B") (pintype "passive"))
      (node (ref "J8") (pin "1") (pinfunction "KL_1") (pintype "passive"))
    )
    (net (code "29") (name "Net-(J9A-S)") (class "Default")
      (node (ref "D6") (pin "A") (pinfunction "A_A") (pintype "passive"))
      (node (ref "J9") (pin "1") (pinfunction "S_1") (pintype "passive"))
      (node (ref "U15") (pin "2") (pinfunction "C_2") (pintype "passive"))
      (node (ref "U15") (pin "4") (pinfunction "C_4") (pintype "passive"))
    )
    (net (code "30") (name "Net-(J9D-S)") (class "Default")
      (node (ref "J9") (pin "4") (pinfunction "S_4") (pintype "passive"))
      (node (ref "Q1") (pin "3") (pinfunction "D_3") (pintype "passive"))
      (node (ref "R2") (pin "1") (pinfunction "1_1") (pintype "passive"))
    )
    (net (code "31") (name "Net-(MDRIVE-TP)") (class "Default")
      (node (ref "C19") (pin "1") (pinfunction "1_1") (pintype "passive"))
      (node (ref "MDRIVE") (pin "P$1") (pinfunction "TP_P$1") (pintype "bidirectional"))
      (node (ref "R15") (pin "2") (pinfunction "2_2") (pintype "passive"))
      (node (ref "U7") (pin "7") (pinfunction "OUT_7") (pintype "output"))
    )
    (net (code "32") (name "Net-(Q2-D)") (class "Default")
      (node (ref "D5") (pin "2") (pinfunction "2_2") (pintype "bidirectional"))
      (node (ref "Q2") (pin "2") (pinfunction "D_2") (pintype "passive"))
      (node (ref "Q3") (pin "2") (pinfunction "D_2") (pintype "passive"))
      (node (ref "Q4") (pin "2") (pinfunction "D_2") (pintype "passive"))
      (node (ref "Q5") (pin "2") (pinfunction "D_2") (pintype "passive"))
    )
    (net (code "33") (name "Net-(Q2-G)") (class "Default")
      (node (ref "Q2") (pin "1") (pinfunction "G_1") (pintype "passive"))
      (node (ref "Q6") (pin "C") (pinfunction "C_C") (pintype "passive"))
      (node (ref "R35") (pin "2") (pinfunction "2_2") (pintype "passive"))
    )
    (net (code "34") (name "Net-(Q2-S)") (class "Default")
      (node (ref "Q2") (pin "3") (pinfunction "S_3") (pintype "passive"))
      (node (ref "Q6") (pin "B") (pinfunction "B_B") (pintype "passive"))
      (node (ref "R22") (pin "2") (pinfunction "2_2") (pintype "passive"))
    )
    (net (code "35") (name "Net-(Q3-G)") (class "Default")
      (node (ref "Q3") (pin "1") (pinfunction "G_1") (pintype "passive"))
      (node (ref "Q7") (pin "C") (pinfunction "C_C") (pintype "passive"))
      (node (ref "R36") (pin "2") (pinfunction "2_2") (pintype "passive"))
    )
    (net (code "36") (name "Net-(Q3-S)") (class "Default")
      (node (ref "Q3") (pin "3") (pinfunction "S_3") (pintype "passive"))
      (node (ref "Q7") (pin "B") (pinfunction "B_B") (pintype "passive"))
      (node (ref "R23") (pin "2") (pinfunction "2_2") (pintype "passive"))
    )
    (net (code "37") (name "Net-(Q4-G)") (class "Default")
      (node (ref "Q4") (pin "1") (pinfunction "G_1") (pintype "passive"))
      (node (ref "Q8") (pin "C") (pinfunction "C_C") (pintype "passive"))
      (node (ref "R37") (pin "2") (pinfunction "2_2") (pintype "passive"))
    )
    (net (code "38") (name "Net-(Q4-S)") (class "Default")
      (node (ref "Q4") (pin "3") (pinfunction "S_3") (pintype "passive"))
      (node (ref "Q8") (pin "B") (pinfunction "B_B") (pintype "passive"))
      (node (ref "R24") (pin "2") (pinfunction "2_2") (pintype "passive"))
    )
    (net (code "39") (name "Net-(Q5-G)") (class "Default")
      (node (ref "Q5") (pin "1") (pinfunction "G_1") (pintype "passive"))
      (node (ref "Q9") (pin "C") (pinfunction "C_C") (pintype "passive"))
      (node (ref "R38") (pin "2") (pinfunction "2_2") (pintype "passive"))
    )
    (net (code "40") (name "Net-(Q5-S)") (class "Default")
      (node (ref "Q5") (pin "3") (pinfunction "S_3") (pintype "passive"))
      (node (ref "Q9") (pin "B") (pinfunction "B_B") (pintype "passive"))
      (node (ref "R25") (pin "2") (pinfunction "2_2") (pintype "passive"))
    )
    (net (code "41") (name "Net-(Q6-PadE)") (class "Default")
      (node (ref "Q6") (pin "E") (pinfunction "E_E") (pintype "passive"))
      (node (ref "R10") (pin "1") (pinfunction "1_1") (pintype "passive"))
    )
    (net (code "42") (name "Net-(Q7-PadE)") (class "Default")
      (node (ref "Q7") (pin "E") (pinfunction "E_E") (pintype "passive"))
      (node (ref "R12") (pin "1") (pinfunction "1_1") (pintype "passive"))
    )
    (net (code "43") (name "Net-(Q8-PadE)") (class "Default")
      (node (ref "Q8") (pin "E") (pinfunction "E_E") (pintype "passive"))
      (node (ref "R26") (pin "1") (pinfunction "1_1") (pintype "passive"))
    )
    (net (code "44") (name "Net-(Q9-PadE)") (class "Default")
      (node (ref "Q9") (pin "E") (pinfunction "E_E") (pintype "passive"))
      (node (ref "R32") (pin "1") (pinfunction "1_1") (pintype "passive"))
    )
    (net (code "45") (name "Net-(Q10-B)") (class "Default")
      (node (ref "C30") (pin "-") (pinfunction "-_-") (pintype "passive"))
      (node (ref "D1") (pin "C") (pinfunction "C_C") (pintype "passive"))
      (node (ref "Q10") (pin "2") (pinfunction "B_2") (pintype "passive"))
      (node (ref "R41") (pin "1") (pinfunction "1_1") (pintype "passive"))
    )
    (net (code "46") (name "Net-(Q10-E)") (class "Default")
      (node (ref "Q10") (pin "3") (pinfunction "E_3") (pintype "passive"))
      (node (ref "R42") (pin "1") (pinfunction "1_1") (pintype "passive"))
    )
    (net (code "47") (name "Net-(R15-Pad1)") (class "Default")
      (node (ref "R15") (pin "1") (pinfunction "1_1") (pintype "passive"))
      (node (ref "R35") (pin "1") (pinfunction "1_1") (pintype "passive"))
      (node (ref "R36") (pin "1") (pinfunction "1_1") (pintype "passive"))
      (node (ref "R37") (pin "1") (pinfunction "1_1") (pintype "passive"))
      (node (ref "R38") (pin "1") (pinfunction "1_1") (pintype "passive"))
    )
    (net (code "48") (name "Net-(RV1-E)") (class "Default")
      (node (ref "C28") (pin "2") (pinfunction "2_2") (pintype "passive"))
      (node (ref "R28") (pin "1") (pinfunction "1_1") (pintype "passive"))
      (node (ref "RV1") (pin "3") (pinfunction "E_3") (pintype "passive"))
      (node (ref "U11") (pin "1") (pinfunction "I_1") (pintype "input"))
    )
    (net (code "49") (name "Net-(RV2-A)") (class "Default")
      (node (ref "RV2") (pin "1") (pinfunction "A_1") (pintype "passive"))
      (node (ref "U13") (pin "1") (pinfunction "CMP1_1") (pintype "passive"))
    )
    (net (code "50") (name "Net-(RV2-E)") (class "Default")
      (node (ref "RV2") (pin "3") (pinfunction "E_3") (pintype "passive"))
      (node (ref "U13") (pin "8") (pinfunction "CMP2_8") (pintype "passive"))
    )
    (net (code "51") (name "Net-(RV3-S)") (class "Default")
      (node (ref "R40") (pin "2") (pinfunction "2_2") (pintype "passive"))
      (node (ref "RV3") (pin "2") (pinfunction "S_2") (pintype "passive"))
    )
    (net (code "52") (name "Net-(RV4-E)") (class "Default")
      (node (ref "R14") (pin "2") (pinfunction "2_2") (pintype "passive"))
      (node (ref "RV4") (pin "3") (pinfunction "E_3") (pintype "passive"))
    )
    (net (code "53") (name "Net-(RV5-E)") (class "Default")
      (node (ref "R45") (pin "2") (pinfunction "2_2") (pintype "passive"))
      (node (ref "RV5") (pin "3") (pinfunction "E_3") (pintype "passive"))
    )
    (net (code "54") (name "Net-(RV5-S)") (class "Default")
      (node (ref "R44") (pin "1") (pinfunction "1_1") (pintype "passive"))
      (node (ref "RV5") (pin "2") (pinfunction "S_2") (pintype "passive"))
    )
    (net (code "55") (name "Net-(TRIGR-TP)") (class "Default")
      (node (ref "TRIGR") (pin "P$1") (pinfunction "TP_P$1") (pintype "bidirectional"))
      (node (ref "U11") (pin "4") (pinfunction "O_4") (pintype "output"))
    )
    (net (code "56") (name "Net-(U2-VO)") (class "Default")
      (node (ref "I5V") (pin "1") (pinfunction "1_1") (pintype "passive"))
      (node (ref "U2") (pin "3") (pinfunction "VO_3") (pintype "passive"))
    )
    (net (code "57") (name "Net-(U5-A0)") (class "Default")
      (node (ref "R18") (pin "2") (pinfunction "2_2") (pintype "passive"))
      (node (ref "U5") (pin "6") (pinfunction "A0_6") (pintype "bidirectional"))
    )
    (net (code "58") (name "Net-(U5-VOUT)") (class "Default")
      (node (ref "R4") (pin "2") (pinfunction "2_2") (pintype "passive"))
      (node (ref "U5") (pin "1") (pinfunction "VOUT_1") (pintype "bidirectional"))
      (node (ref "U7") (pin "3") (pinfunction "+IN_3") (pintype "input"))
      (node (ref "VREG") (pin "P$1") (pinfunction "TP_P$1") (pintype "bidirectional"))
    )
    (net (code "59") (name "Net-(U7A--IN)") (class "Default")
      (node (ref "R6") (pin "2") (pinfunction "2_2") (pintype "passive"))
      (node (ref "U7") (pin "1") (pinfunction "OUT_1") (pintype "output"))
      (node (ref "U7") (pin "2") (pinfunction "-IN_2") (pintype "input"))
    )
    (net (code "60") (name "Net-(U7C--IN)") (class "Default")
      (node (ref "R5") (pin "2") (pinfunction "2_2") (pintype "passive"))
      (node (ref "U7") (pin "8") (pinfunction "OUT_8") (pintype "output"))
      (node (ref "U7") (pin "9") (pinfunction "-IN_9") (pintype "input"))
    )
    (net (code "61") (name "Net-(U7D-+IN)") (class "Default")
      (node (ref "R16") (pin "1") (pinfunction "1_1") (pintype "passive"))
      (node (ref "U7") (pin "12") (pinfunction "+IN_12") (pintype "input"))
    )
    (net (code "62") (name "Net-(U7D--IN)") (class "Default")
      (node (ref "R9") (pin "1") (pinfunction "1_1") (pintype "passive"))
      (node (ref "U7") (pin "13") (pinfunction "-IN_13") (pintype "input"))
      (node (ref "U7") (pin "14") (pinfunction "OUT_14") (pintype "output"))
    )
    (net (code "63") (name "Net-(U8-X1)") (class "Default")
      (node (ref "C22") (pin "1") (pinfunction "1_1") (pintype "passive"))
      (node (ref "U8") (pin "1") (pinfunction "X1_1") (pintype "bidirectional"))
      (node (ref "Y1") (pin "1") (pinfunction "P$1_1") (pintype "bidirectional"))
    )
    (net (code "64") (name "Net-(U8-X2)") (class "Default")
      (node (ref "C23") (pin "1") (pinfunction "1_1") (pintype "passive"))
      (node (ref "U8") (pin "2") (pinfunction "X2_2") (pintype "bidirectional"))
      (node (ref "Y1") (pin "2") (pinfunction "P$2_2") (pintype "bidirectional"))
    )
    (net (code "65") (name "Net-(U9-TRIM{slash}NR)") (class "Default")
      (node (ref "R44") (pin "2") (pinfunction "2_2") (pintype "passive"))
      (node (ref "U9") (pin "5") (pinfunction "TRIM/NR_5") (pintype "bidirectional"))
    )
    (net (code "66") (name "Net-(U10-C)") (class "Default")
      (node (ref "D4") (pin "A") (pinfunction "A_A") (pintype "passive"))
      (node (ref "R21") (pin "2") (pinfunction "2_2") (pintype "passive"))
      (node (ref "U10") (pin "2") (pinfunction "C_2") (pintype "passive"))
    )
    (net (code "67") (name "Net-(U10-EMI)") (class "Default")
      (node (ref "C28") (pin "1") (pinfunction "1_1") (pintype "passive"))
      (node (ref "R27") (pin "2") (pinfunction "2_2") (pintype "passive"))
      (node (ref "U10") (pin "4") (pinfunction "EMI_4") (pintype "passive"))
    )
    (net (code "68") (name "Net-(U12-CAP+)") (class "Default")
      (node (ref "C4") (pin "2") (pinfunction "2_2") (pintype "passive"))
      (node (ref "U12") (pin "2") (pinfunction "CAP+_2") (pintype "bidirectional"))
    )
    (net (code "69") (name "Net-(U12-CAP-)") (class "Default")
      (node (ref "C4") (pin "1") (pinfunction "1_1") (pintype "passive"))
      (node (ref "U12") (pin "4") (pinfunction "CAP-_4") (pintype "bidirectional"))
    )
    (net (code "70") (name "Net-(U13-+IN)") (class "Default")
      (node (ref "R31") (pin "2") (pinfunction "2_2") (pintype "passive"))
      (node (ref "R34") (pin "1") (pinfunction "1_1") (pintype "passive"))
      (node (ref "U13") (pin "3") (pinfunction "+IN_3") (pintype "input"))
    )
    (net (code "71") (name "Net-(U13--IN)") (class "Default")
      (node (ref "R13") (pin "2") (pinfunction "2_2") (pintype "passive"))
      (node (ref "R33") (pin "1") (pinfunction "1_1") (pintype "passive"))
      (node (ref "U13") (pin "2") (pinfunction "-IN_2") (pintype "input"))
    )
    (net (code "72") (name "Net-(U13-OUT)") (class "Default")
      (node (ref "R11") (pin "2") (pinfunction "2_2") (pintype "passive"))
      (node (ref "R13") (pin "1") (pinfunction "1_1") (pintype "passive"))
      (node (ref "U13") (pin "6") (pinfunction "OUT_6") (pintype "output"))
      (node (ref "U7") (pin "10") (pinfunction "+IN_10") (pintype "input"))
    )
    (net (code "73") (name "Net-(U15-B)") (class "Default")
      (node (ref "R1") (pin "2") (pinfunction "2_2") (pintype "passive"))
      (node (ref "U15") (pin "1") (pinfunction "B_1") (pintype "passive"))
    )
    (net (code "74") (name "Net-(X1J-KL)") (class "Default")
      (node (ref "J-SP1") (pin "1") (pinfunction "1_1") (pintype "passive"))
      (node (ref "X1") (pin "18") (pinfunction "KL_18") (pintype "passive"))
    )
    (net (code "75") (name "ONOFF-BTN") (class "Default")
      (node (ref "U$1") (pin "D19") (pinfunction "D19_D19") (pintype "bidirectional"))
      (node (ref "X1") (pin "2") (pinfunction "KL_2") (pintype "passive"))
    )
    (net (code "76") (name "ONOFF-FB") (class "Default")
      (node (ref "U$1") (pin "D15") (pinfunction "D15_D15") (pintype "bidirectional"))
      (node (ref "X1") (pin "3") (pinfunction "KL_3") (pintype "passive"))
    )
    (net (code "77") (name "RTC-MFP") (class "Default")
      (node (ref "U$1") (pin "A0") (pinfunction "A0_A0") (pintype "bidirectional"))
      (node (ref "U8") (pin "7") (pinfunction "MFP_7") (pintype "bidirectional"))
    )
    (net (code "78") (name "SLCD-CS") (class "Default")
      (node (ref "U$1") (pin "D3") (pinfunction "D3_D3") (pintype "bidirectional"))
      (node (ref "X1") (pin "13") (pinfunction "KL_13") (pintype "passive"))
    )
    (net (code "79") (name "SLCD-DC") (class "Default")
      (node (ref "U$1") (pin "D1") (pinfunction "D1_D1") (pintype "bidirectional"))
      (node (ref "X1") (pin "14") (pinfunction "KL_14") (pintype "passive"))
    )
    (net (code "80") (name "SLCD-RST") (class "Default")
      (node (ref "U$1") (pin "D0") (pinfunction "D0_D0") (pintype "bidirectional"))
      (node (ref "X1") (pin "15") (pinfunction "KL_15") (pintype "passive"))
    )
    (net (code "81") (name "SPI-CLK") (class "Default")
      (node (ref "U$1") (pin "D7") (pinfunction "D7_SCK_D7") (pintype "bidirectional"))
      (node (ref "X1") (pin "11") (pinfunction "KL_11") (pintype "passive"))
    )
    (net (code "82") (name "SPI-MO") (class "Default")
      (node (ref "U$1") (pin "D5") (pinfunction "D5_MOSI_D5") (pintype "bidirectional"))
      (node (ref "X1") (pin "12") (pinfunction "KL_12") (pintype "passive"))
    )
    (net (code "83") (name "TEMP-SENSE") (class "Default")
      (node (ref "U$1") (pin "A6") (pinfunction "A6_A6") (pintype "bidirectional"))
      (node (ref "U4") (pin "3") (pinfunction "OUT_3") (pintype "output"))
    )
    (net (code "84") (name "TRG-NEG") (class "Default")
      (node (ref "R21") (pin "1") (pinfunction "1_1") (pintype "passive"))
      (node (ref "X1") (pin "16") (pinfunction "KL_16") (pintype "passive"))
    )
    (net (code "85") (name "TRG-POS") (class "Default")
      (node (ref "D4") (pin "C") (pinfunction "C_C") (pintype "passive"))
      (node (ref "U10") (pin "1") (pinfunction "A_1") (pintype "passive"))
      (node (ref "X1") (pin "17") (pinfunction "KL_17") (pintype "passive"))
    )
    (net (code "86") (name "TRIGGER-IN") (class "Default")
      (node (ref "R29") (pin "1") (pinfunction "1_1") (pintype "passive"))
      (node (ref "U$1") (pin "A3") (pinfunction "A3_A3") (pintype "bidirectional"))
      (node (ref "U11") (pin "3") (pinfunction "I_3") (pintype "input"))
      (node (ref "U11") (pin "6") (pinfunction "O_6") (pintype "output"))
    )
    (net (code "87") (name "VS-BTN") (class "Default")
      (node (ref "U$1") (pin "D14") (pinfunction "D14_D14") (pintype "bidirectional"))
      (node (ref "X1") (pin "10") (pinfunction "KL_10") (pintype "passive"))
    )
    (net (code "88") (name "VS-EXT") (class "Default")
      (node (ref "U$1") (pin "D13") (pinfunction "D13_D13") (pintype "bidirectional"))
      (node (ref "X1") (pin "9") (pinfunction "KL_9") (pintype "passive"))
    )
    (net (code "89") (name "VS-NEG") (class "Default")
      (node (ref "R33") (pin "2") (pinfunction "2_2") (pintype "passive"))
      (node (ref "X1") (pin "7") (pinfunction "KL_7") (pintype "passive"))
    )
    (net (code "90") (name "VS-POS") (class "Default")
      (node (ref "R34") (pin "2") (pinfunction "2_2") (pintype "passive"))
      (node (ref "X1") (pin "8") (pinfunction "KL_8") (pintype "passive"))
    )
    (net (code "91") (name "VSENSE") (class "Default")
      (node (ref "C15") (pin "1") (pinfunction "1_1") (pintype "passive"))
      (node (ref "R43") (pin "1") (pinfunction "1_1") (pintype "passive"))
      (node (ref "R5") (pin "1") (pinfunction "1_1") (pintype "passive"))
      (node (ref "U6") (pin "1") (pinfunction "CH1+_1") (pintype "bidirectional"))
    )
    (net (code "92") (name "unconnected-(U$1-D4_SS-PadD4)") (class "Default")
      (node (ref "U$1") (pin "D4") (pinfunction "D4_SS_D4") (pintype "bidirectional"))
    )
    (net (code "93") (name "unconnected-(U$1-D6_MISO-PadD6)") (class "Default")
      (node (ref "U$1") (pin "D6") (pinfunction "D6_MISO_D6") (pintype "bidirectional"))
    )
    (net (code "94") (name "unconnected-(U$1-D8_RX0-PadD8)") (class "Default")
      (node (ref "U$1") (pin "D8") (pinfunction "D8_RX0_D8") (pintype "bidirectional"))
    )
    (net (code "95") (name "unconnected-(U$1-D9_TX0-PadD9)") (class "Default")
      (node (ref "U$1") (pin "D9") (pinfunction "D9_TX0_D9") (pintype "bidirectional"))
    )
    (net (code "96") (name "unconnected-(U$1-PadA2)") (class "Default")
      (node (ref "U$1") (pin "A2") (pinfunction "A2_A2") (pintype "bidirectional"))
    )
    (net (code "97") (name "unconnected-(U$1-PadA4)") (class "Default")
      (node (ref "U$1") (pin "A4") (pinfunction "A4_A4") (pintype "bidirectional"))
    )
    (net (code "98") (name "unconnected-(U$1-PadA5)") (class "Default")
      (node (ref "U$1") (pin "A5") (pinfunction "A5_A5") (pintype "bidirectional"))
    )
    (net (code "99") (name "unconnected-(U$1-PadA7)") (class "Default")
      (node (ref "U$1") (pin "A7") (pinfunction "A7_A7") (pintype "bidirectional"))
    )
    (net (code "100") (name "unconnected-(U$1-PadAREF)") (class "Default")
      (node (ref "U$1") (pin "AREF") (pinfunction "AREF_AREF") (pintype "bidirectional"))
    )
    (net (code "101") (name "unconnected-(U$1-PadD2)") (class "Default")
      (node (ref "U$1") (pin "D2") (pinfunction "D2_D2") (pintype "bidirectional"))
    )
    (net (code "102") (name "unconnected-(U$1-PadD18)") (class "Default")
      (node (ref "U$1") (pin "D18") (pinfunction "D18_D18") (pintype "bidirectional"))
    )
    (net (code "103") (name "unconnected-(U$1-PadD23)") (class "Default")
      (node (ref "U$1") (pin "D23") (pinfunction "D23_D23") (pintype "bidirectional"))
    )
    (net (code "104") (name "unconnected-(U$1-PadRST)") (class "Default")
      (node (ref "U$1") (pin "RST") (pinfunction "RST_RST") (pintype "bidirectional"))
    )
    (net (code "105") (name "unconnected-(U9-DNC_1-Pad1)") (class "Default")
      (node (ref "U9") (pin "1") (pinfunction "DNC_1_1") (pintype "bidirectional"))
    )
    (net (code "106") (name "unconnected-(U9-DNC_2-Pad8)") (class "Default")
      (node (ref "U9") (pin "8") (pinfunction "DNC_2_8") (pintype "bidirectional"))
    )
    (net (code "107") (name "unconnected-(U9-NC-Pad7)") (class "Default")
      (node (ref "U9") (pin "7") (pinfunction "NC_7") (pintype "no_connect"))
    )
    (net (code "108") (name "unconnected-(U9-TEMP-Pad3)") (class "Default")
      (node (ref "U9") (pin "3") (pinfunction "TEMP_3") (pintype "bidirectional"))
    )
    (net (code "109") (name "unconnected-(U10-BAS-Pad6)") (class "Default")
      (node (ref "U10") (pin "6") (pinfunction "BAS_6") (pintype "passive"))
    )
    (net (code "110") (name "unconnected-(U12-BOOST-Pad1)") (class "Default")
      (node (ref "U12") (pin "1") (pinfunction "BOOST_1") (pintype "bidirectional"))
    )
    (net (code "111") (name "unconnected-(U12-LV-Pad6)") (class "Default")
      (node (ref "U12") (pin "6") (pinfunction "LV_6") (pintype "bidirectional"))
    )
    (net (code "112") (name "unconnected-(U12-OSC-Pad7)") (class "Default")
      (node (ref "U12") (pin "7") (pinfunction "OSC_7") (pintype "bidirectional"))
    )
  )
)
